# train.net
KiCad netlist of a schematic drawn in EAGLE
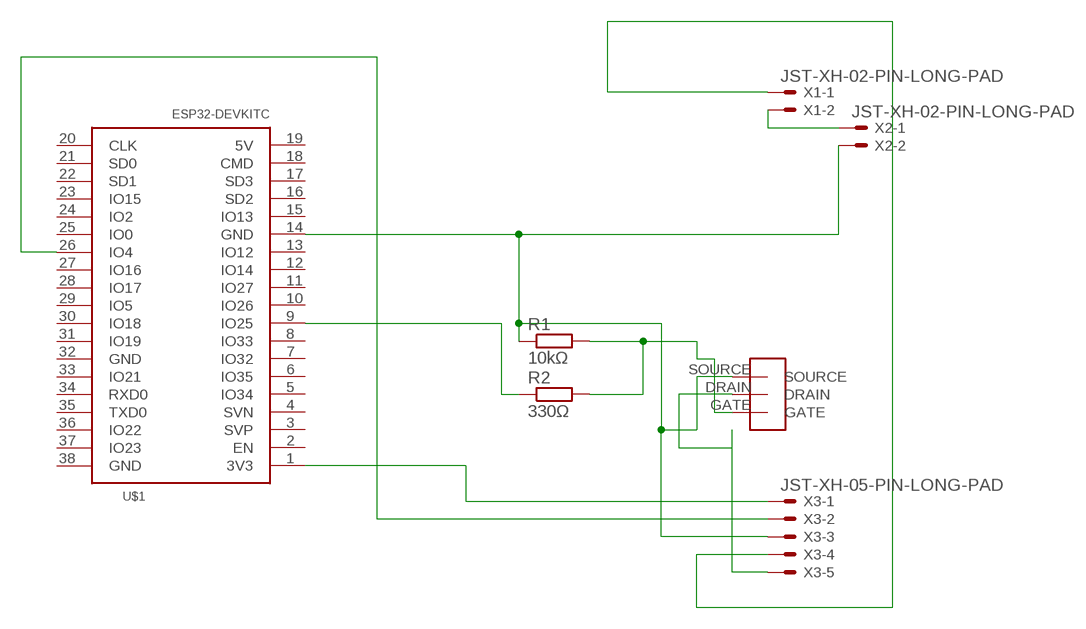
[diagram p0: schematic, sheet 1]

(export (version "E")
  (design (tool "Eeschema 10.0.6"))
  (components
    (comp (ref "FET1")
      (value "FET")
      (footprint "eagle-import:FET")
      (libsource (lib "eagle-import") (part "FET"))
    )
    (comp (ref "R1")
      (value "10kΩ")
      (footprint "eagle-import:0207_10")
      (libsource (lib "eagle-import") (part "R-EU_0207/10"))
    )
    (comp (ref "R2")
      (value "330Ω")
      (footprint "eagle-import:0207_10")
      (libsource (lib "eagle-import") (part "R-EU_0207/10"))
    )
    (comp (ref "U$1")
      (value "ESP32DEVKITC")
      (footprint "eagle-import:ESP32-DEVKITC")
      (libsource (lib "eagle-import") (part "ESP32DEVKITC"))
    )
    (comp (ref "X1")
      (value "JST-XH-02-PIN-LONG-PAD")
      (footprint "eagle-import:JST-XH-02-PACKAGE-LONG-PAD")
      (libsource (lib "eagle-import") (part "JST-XH-02-PIN-LONG-PAD"))
    )
    (comp (ref "X2")
      (value "JST-XH-02-PIN-LONG-PAD")
      (footprint "eagle-import:JST-XH-02-PACKAGE-LONG-PAD")
      (libsource (lib "eagle-import") (part "JST-XH-02-PIN-LONG-PAD"))
    )
    (comp (ref "X3")
      (value "JST-XH-05-PIN-LONG-PAD")
      (footprint "eagle-import:JST-XH-05-PACKAGE-LONG-PAD")
      (libsource (lib "eagle-import") (part "JST-XH-05-PIN-LONG-PAD"))
    )
  )
  (nets
    (net (code "1") (name "Net-(FET1-PadGATE)") (class "Default")
      (node (ref "FET1") (pin "GATE") (pinfunction "GATE_GATE") (pintype "bidirectional"))
      (node (ref "R1") (pin "2") (pinfunction "2_2") (pintype "passive"))
      (node (ref "R2") (pin "2") (pinfunction "2_2") (pintype "passive"))
    )
    (net (code "2") (name "Net-(U$1-3V3)") (class "Default")
      (node (ref "U$1") (pin "1") (pinfunction "3V3_1") (pintype "bidirectional"))
      (node (ref "X3") (pin "1") (pinfunction "S_1") (pintype "passive"))
    )
    (net (code "3") (name "Net-(U$1-IO4)") (class "Default")
      (node (ref "U$1") (pin "26") (pinfunction "IO4_26") (pintype "bidirectional"))
      (node (ref "X3") (pin "2") (pinfunction "S_2") (pintype "passive"))
    )
    (net (code "4") (name "Net-(U$1-IO25)") (class "Default")
      (node (ref "R2") (pin "1") (pinfunction "1_1") (pintype "passive"))
      (node (ref "U$1") (pin "9") (pinfunction "IO25_9") (pintype "bidirectional"))
    )
    (net (code "5") (name "Net-(X1A-S)") (class "Default")
      (node (ref "X1") (pin "1") (pinfunction "S_1") (pintype "passive"))
      (node (ref "X3") (pin "4") (pinfunction "S_4") (pintype "passive"))
    )
    (net (code "6") (name "Net-(X1B-S)") (class "Default")
      (node (ref "X1") (pin "2") (pinfunction "S_2") (pintype "passive"))
      (node (ref "X2") (pin "1") (pinfunction "S_1") (pintype "passive"))
    )
    (net (code "7") (name "Net-(X2B-S)") (class "Default")
      (node (ref "FET1") (pin "SOURCE") (pinfunction "SOURCE_SOURCE") (pintype "bidirectional"))
      (node (ref "R1") (pin "1") (pinfunction "1_1") (pintype "passive"))
      (node (ref "U$1") (pin "14") (pinfunction "GND_14") (pintype "bidirectional"))
      (node (ref "X2") (pin "2") (pinfunction "S_2") (pintype "passive"))
      (node (ref "X3") (pin "3") (pinfunction "S_3") (pintype "passive"))
    )
    (net (code "8") (name "Net-(X3E-S)") (class "Default")
      (node (ref "FET1") (pin "DRAIN") (pinfunction "DRAIN_DRAIN") (pintype "bidirectional"))
      (node (ref "X3") (pin "5") (pinfunction "S_5") (pintype "passive"))
    )
    (net (code "9") (name "unconnected-(U$1-5V-Pad19)") (class "Default")
      (node (ref "U$1") (pin "19") (pinfunction "5V_19") (pintype "bidirectional"))
    )
    (net (code "10") (name "unconnected-(U$1-CLK-Pad20)") (class "Default")
      (node (ref "U$1") (pin "20") (pinfunction "CLK_20") (pintype "bidirectional"))
    )
    (net (code "11") (name "unconnected-(U$1-CMD-Pad18)") (class "Default")
      (node (ref "U$1") (pin "18") (pinfunction "CMD_18") (pintype "bidirectional"))
    )
    (net (code "12") (name "unconnected-(U$1-EN-Pad2)") (class "Default")
      (node (ref "U$1") (pin "2") (pinfunction "EN_2") (pintype "bidirectional"))
    )
    (net (code "13") (name "unconnected-(U$1-GND-Pad32)") (class "Default")
      (node (ref "U$1") (pin "32") (pinfunction "GND_32") (pintype "bidirectional"))
    )
    (net (code "14") (name "unconnected-(U$1-GND-Pad38)") (class "Default")
      (node (ref "U$1") (pin "38") (pinfunction "GND_38") (pintype "bidirectional"))
    )
    (net (code "15") (name "unconnected-(U$1-IO0-Pad25)") (class "Default")
      (node (ref "U$1") (pin "25") (pinfunction "IO0_25") (pintype "bidirectional"))
    )
    (net (code "16") (name "unconnected-(U$1-IO2-Pad24)") (class "Default")
      (node (ref "U$1") (pin "24") (pinfunction "IO2_24") (pintype "bidirectional"))
    )
    (net (code "17") (name "unconnected-(U$1-IO5-Pad29)") (class "Default")
      (node (ref "U$1") (pin "29") (pinfunction "IO5_29") (pintype "bidirectional"))
    )
    (net (code "18") (name "unconnected-(U$1-IO12-Pad13)") (class "Default")
      (node (ref "U$1") (pin "13") (pinfunction "IO12_13") (pintype "bidirectional"))
    )
    (net (code "19") (name "unconnected-(U$1-IO13-Pad15)") (class "Default")
      (node (ref "U$1") (pin "15") (pinfunction "IO13_15") (pintype "bidirectional"))
    )
    (net (code "20") (name "unconnected-(U$1-IO14-Pad12)") (class "Default")
      (node (ref "U$1") (pin "12") (pinfunction "IO14_12") (pintype "bidirectional"))
    )
    (net (code "21") (name "unconnected-(U$1-IO15-Pad23)") (class "Default")
      (node (ref "U$1") (pin "23") (pinfunction "IO15_23") (pintype "bidirectional"))
    )
    (net (code "22") (name "unconnected-(U$1-IO16-Pad27)") (class "Default")
      (node (ref "U$1") (pin "27") (pinfunction "IO16_27") (pintype "bidirectional"))
    )
    (net (code "23") (name "unconnected-(U$1-IO17-Pad28)") (class "Default")
      (node (ref "U$1") (pin "28") (pinfunction "IO17_28") (pintype "bidirectional"))
    )
    (net (code "24") (name "unconnected-(U$1-IO18-Pad30)") (class "Default")
      (node (ref "U$1") (pin "30") (pinfunction "IO18_30") (pintype "bidirectional"))
    )
    (net (code "25") (name "unconnected-(U$1-IO19-Pad31)") (class "Default")
      (node (ref "U$1") (pin "31") (pinfunction "IO19_31") (pintype "bidirectional"))
    )
    (net (code "26") (name "unconnected-(U$1-IO21-Pad33)") (class "Default")
      (node (ref "U$1") (pin "33") (pinfunction "IO21_33") (pintype "bidirectional"))
    )
    (net (code "27") (name "unconnected-(U$1-IO22-Pad36)") (class "Default")
      (node (ref "U$1") (pin "36") (pinfunction "IO22_36") (pintype "bidirectional"))
    )
    (net (code "28") (name "unconnected-(U$1-IO23-Pad37)") (class "Default")
      (node (ref "U$1") (pin "37") (pinfunction "IO23_37") (pintype "bidirectional"))
    )
    (net (code "29") (name "unconnected-(U$1-IO26-Pad10)") (class "Default")
      (node (ref "U$1") (pin "10") (pinfunction "IO26_10") (pintype "bidirectional"))
    )
    (net (code "30") (name "unconnected-(U$1-IO27-Pad11)") (class "Default")
      (node (ref "U$1") (pin "11") (pinfunction "IO27_11") (pintype "bidirectional"))
    )
    (net (code "31") (name "unconnected-(U$1-IO32-Pad7)") (class "Default")
      (node (ref "U$1") (pin "7") (pinfunction "IO32_7") (pintype "bidirectional"))
    )
    (net (code "32") (name "unconnected-(U$1-IO33-Pad8)") (class "Default")
      (node (ref "U$1") (pin "8") (pinfunction "IO33_8") (pintype "bidirectional"))
    )
    (net (code "33") (name "unconnected-(U$1-IO34-Pad5)") (class "Default")
      (node (ref "U$1") (pin "5") (pinfunction "IO34_5") (pintype "bidirectional"))
    )
    (net (code "34") (name "unconnected-(U$1-IO35-Pad6)") (class "Default")
      (node (ref "U$1") (pin "6") (pinfunction "IO35_6") (pintype "bidirectional"))
    )
    (net (code "35") (name "unconnected-(U$1-RXD0-Pad34)") (class "Default")
      (node (ref "U$1") (pin "34") (pinfunction "RXD0_34") (pintype "bidirectional"))
    )
    (net (code "36") (name "unconnected-(U$1-SD0-Pad21)") (class "Default")
      (node (ref "U$1") (pin "21") (pinfunction "SD0_21") (pintype "bidirectional"))
    )
    (net (code "37") (name "unconnected-(U$1-SD1-Pad22)") (class "Default")
      (node (ref "U$1") (pin "22") (pinfunction "SD1_22") (pintype "bidirectional"))
    )
    (net (code "38") (name "unconnected-(U$1-SD2-Pad16)") (class "Default")
      (node (ref "U$1") (pin "16") (pinfunction "SD2_16") (pintype "bidirectional"))
    )
    (net (code "39") (name "unconnected-(U$1-SD3-Pad17)") (class "Default")
      (node (ref "U$1") (pin "17") (pinfunction "SD3_17") (pintype "bidirectional"))
    )
    (net (code "40") (name "unconnected-(U$1-SVN-Pad4)") (class "Default")
      (node (ref "U$1") (pin "4") (pinfunction "SVN_4") (pintype "bidirectional"))
    )
    (net (code "41") (name "unconnected-(U$1-SVP-Pad3)") (class "Default")
      (node (ref "U$1") (pin "3") (pinfunction "SVP_3") (pintype "bidirectional"))
    )
    (net (code "42") (name "unconnected-(U$1-TXD0-Pad35)") (class "Default")
      (node (ref "U$1") (pin "35") (pinfunction "TXD0_35") (pintype "bidirectional"))
    )
  )
)
